# IDC_MCX_Adapter.net
KiCad netlist of a schematic drawn in Altium Designer
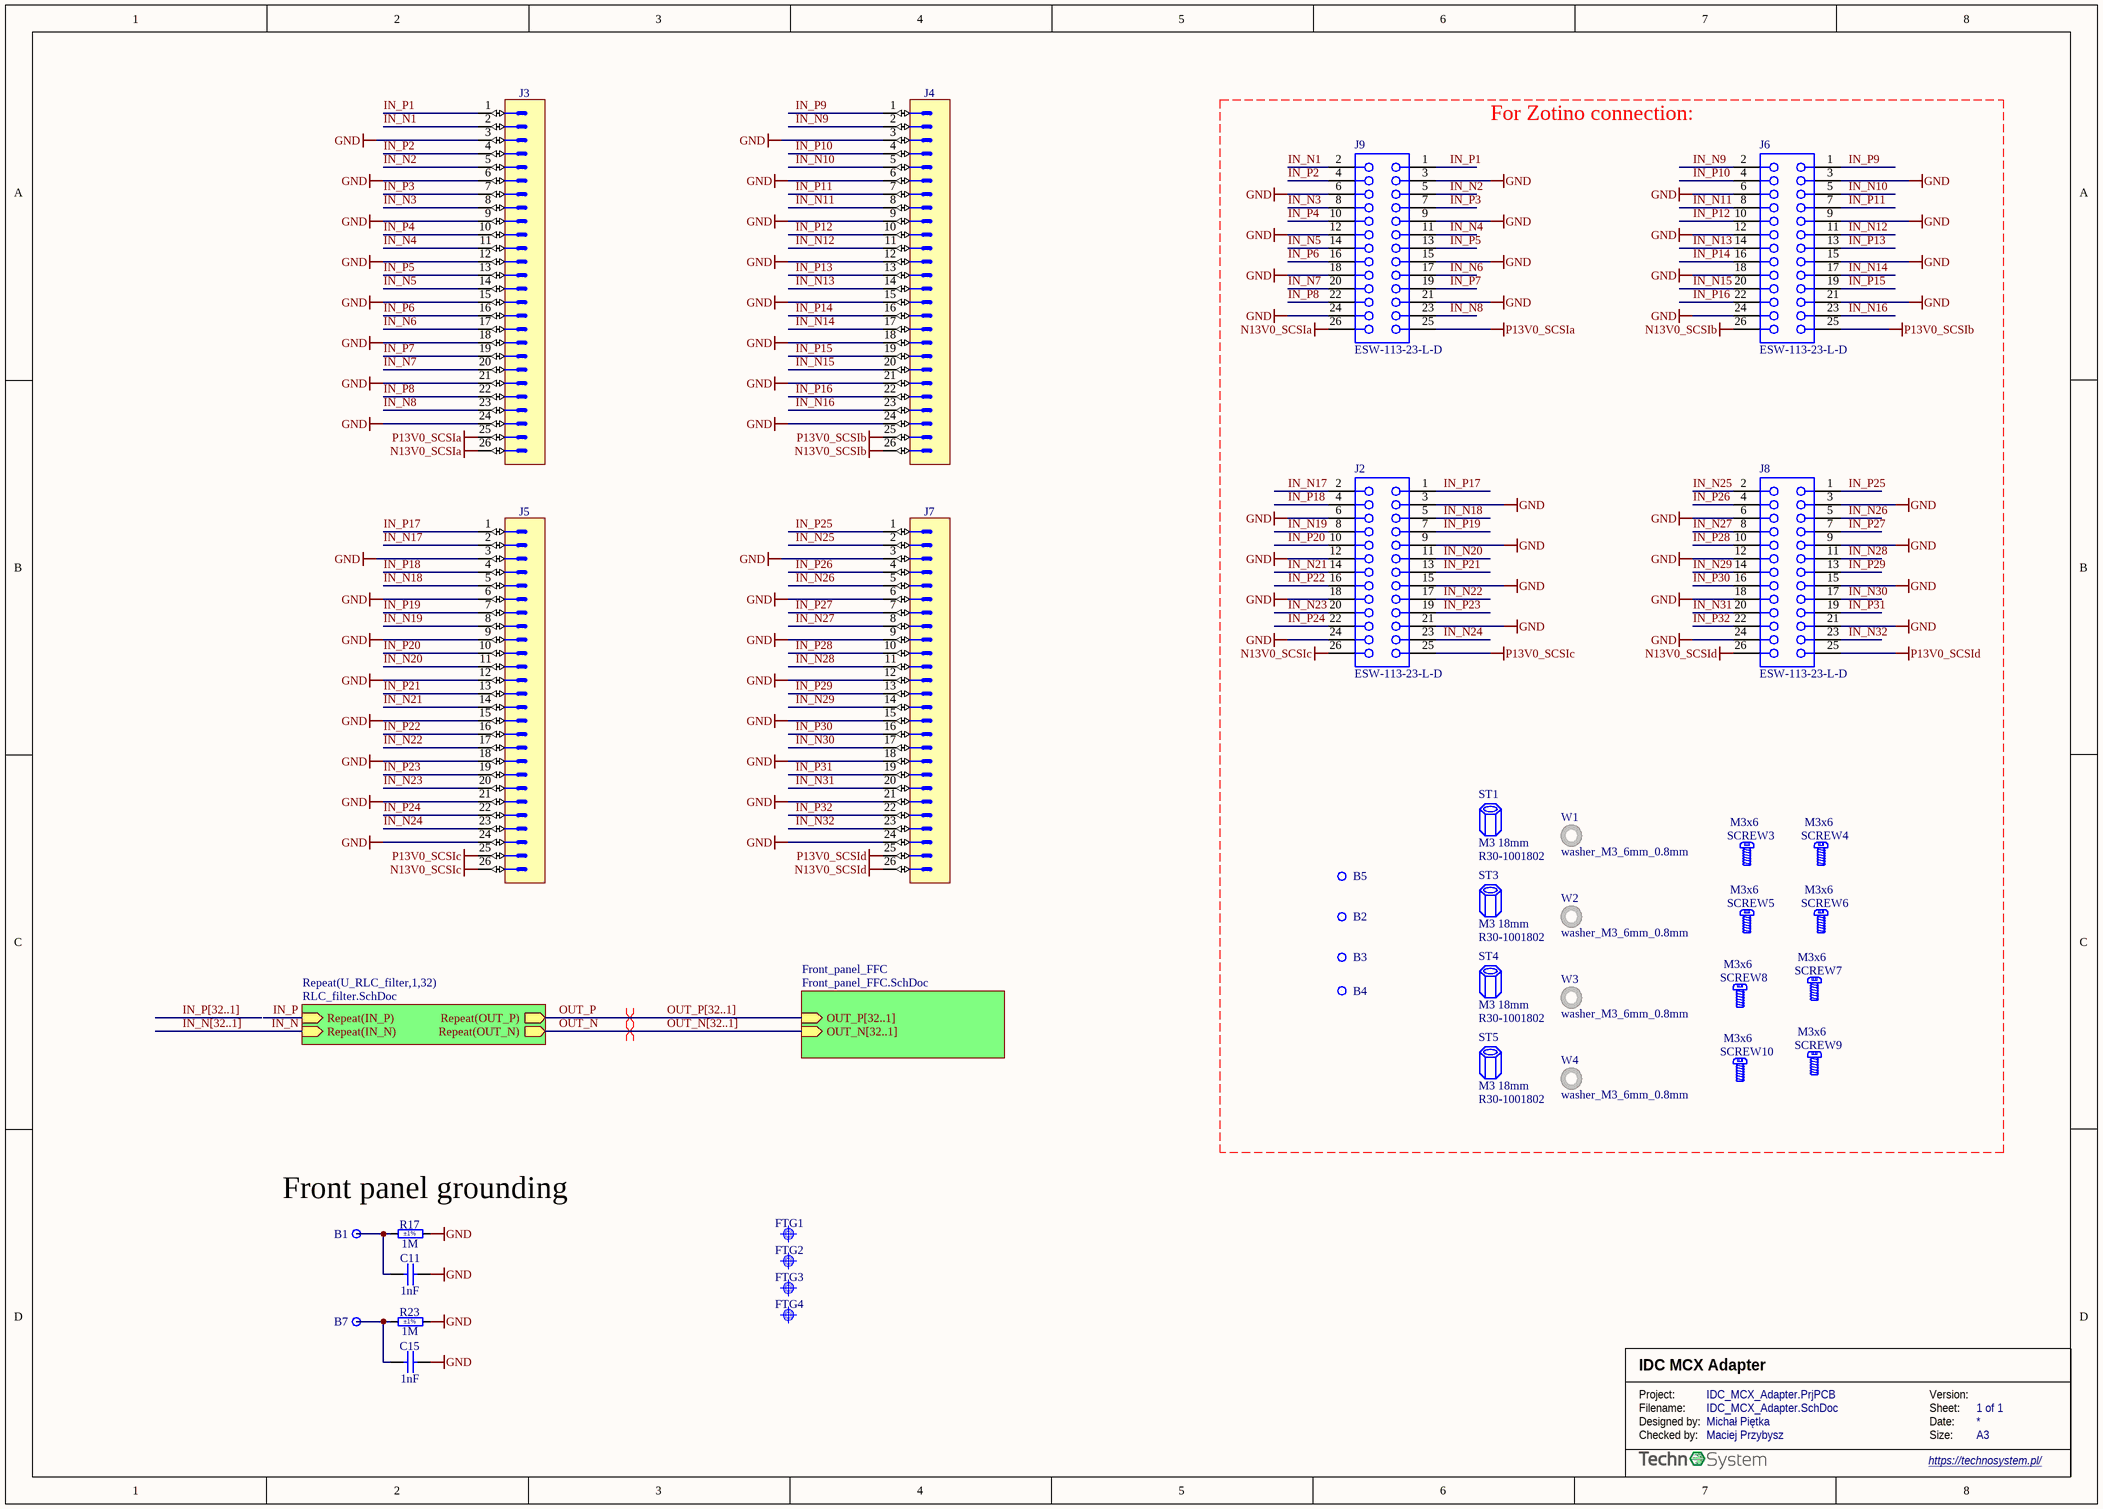
[diagram p0: IDC_MCX_Adapter.SchDoc]

(export (version "E")
  (design (tool "Eeschema 10.0.6"))
  (components
    (comp (ref "B1")
      (value "Plated Hole")
      (footprint "MTG270_500")
      (description "Single Terminal Socket")
      (fields (field (name "PART NUMBER") "PLATED_HOLE2.7_PAD5.0") (field (name "AUTHOR") "CERN DEM JMW"))
      (libsource (lib "Eletro-mechanical") (part "Single Terminal Socket"))
    )
    (comp (ref "B2")
      (value "Plated Hole")
      (footprint "MTG320_700")
      (description "Single Terminal Socket")
      (fields (field (name "PART NUMBER") "PLATED_HOLE3.2_PAD7.0") (field (name "AUTHOR") "CERN DEM JMW"))
      (libsource (lib "Eletro-mechanical") (part "Single Terminal Socket"))
    )
    (comp (ref "B3")
      (value "Plated Hole")
      (footprint "MTG320_700")
      (description "Single Terminal Socket")
      (fields (field (name "PART NUMBER") "PLATED_HOLE3.2_PAD7.0") (field (name "AUTHOR") "CERN DEM JMW"))
      (libsource (lib "Eletro-mechanical") (part "Single Terminal Socket"))
    )
    (comp (ref "B4")
      (value "Plated Hole")
      (footprint "MTG320_700")
      (description "Single Terminal Socket")
      (fields (field (name "PART NUMBER") "PLATED_HOLE3.2_PAD7.0") (field (name "AUTHOR") "CERN DEM JMW"))
      (libsource (lib "Eletro-mechanical") (part "Single Terminal Socket"))
    )
    (comp (ref "B5")
      (value "Plated Hole")
      (footprint "MTG320_700")
      (description "Single Terminal Socket")
      (fields (field (name "PART NUMBER") "PLATED_HOLE3.2_PAD7.0") (field (name "AUTHOR") "CERN DEM JMW"))
      (libsource (lib "Eletro-mechanical") (part "Single Terminal Socket"))
    )
    (comp (ref "B7")
      (value "Plated Hole")
      (footprint "MTG270_500")
      (description "Single Terminal Socket")
      (fields (field (name "PART NUMBER") "PLATED_HOLE2.7_PAD5.0") (field (name "AUTHOR") "CERN DEM JMW"))
      (libsource (lib "Eletro-mechanical") (part "Single Terminal Socket"))
    )
    (comp (ref "C11")
      (value "1nF")
      (footprint "CAPC1608X87N")
      (description "Non-polarised capacitor")
      (fields
        (field (name "PART NUMBER") "CC0603_1NF_50V_10%_X7R")
        (field (name "MANUFACTURER") "GENERIC")
        (field (name "AUTHOR") "CERN DEM JLC")
      )
      (libsource (lib "Capacitors") (part "Capacitor - non polarized"))
    )
    (comp (ref "C15")
      (value "1nF")
      (footprint "CAPC1608X87N")
      (description "Non-polarised capacitor")
      (fields
        (field (name "PART NUMBER") "CC0603_1NF_50V_10%_X7R")
        (field (name "MANUFACTURER") "GENERIC")
        (field (name "AUTHOR") "CERN DEM JLC")
      )
      (libsource (lib "Capacitors") (part "Capacitor - non polarized"))
    )
    (comp (ref "FTG1")
      (value "Use only in PCB")
      (footprint "FIDUCIAL_TOP_C100-200")
      (description "Fiducial Target")
      (fields (field (name "PART NUMBER") "FIDUCIAL_TARGET_C100-200") (field (name "AUTHOR") "CERN DEM JLC"))
      (libsource (lib "Eletro-mechanical") (part "Fiducial Target"))
    )
    (comp (ref "FTG2")
      (value "Use only in PCB")
      (footprint "FIDUCIAL_TOP_S100-200")
      (description "Fiducial Target")
      (fields (field (name "PART NUMBER") "FIDUCIAL_TARGET_S100-200") (field (name "AUTHOR") "CERN DEM JLC"))
      (libsource (lib "Eletro-mechanical") (part "Fiducial Target"))
    )
    (comp (ref "FTG3")
      (value "Use only in PCB")
      (footprint "FIDUCIAL_TOP_S100-200")
      (description "Fiducial Target")
      (fields (field (name "PART NUMBER") "FIDUCIAL_TARGET_S100-200") (field (name "AUTHOR") "CERN DEM JLC"))
      (libsource (lib "Eletro-mechanical") (part "Fiducial Target"))
    )
    (comp (ref "FTG4")
      (value "Use only in PCB")
      (footprint "FIDUCIAL_TOP_S100-200")
      (description "Fiducial Target")
      (fields (field (name "PART NUMBER") "FIDUCIAL_TARGET_S100-200") (field (name "AUTHOR") "CERN DEM JLC"))
      (libsource (lib "Eletro-mechanical") (part "Fiducial Target"))
    )
    (comp (ref "J2")
      (value "ESW-113-23-L-D")
      (footprint "SMTC-ESW-113-23-X-D")
      (description "Elevated Socket, Through-hole, Vertical, -55 to 125 degC, 2.54 mm Pitch, 26-Pin, Female, RoHS")
      (fields (field (name "MANUFACTURER") "Samtec"))
      (libsource (lib "Altium Content Vault") (part "SMTC-ESW-113-X-X-D"))
    )
    (comp (ref "J3")
      (value "Header 26")
      (footprint "3M_N2526-6002RB")
      (description "Connector 26 Male")
      (fields
        (field (name "PART NUMBER") "3M_N2526-6002RB")
        (field (name "MANUFACTURER") "3M")
        (field (name "AUTHOR") "CERN DEM JLC")
      )
      (libsource (lib "Connectors") (part "Connector 26 Male"))
    )
    (comp (ref "J4")
      (value "Header 26")
      (footprint "3M_N2526-6002RB")
      (description "Connector 26 Male")
      (fields
        (field (name "PART NUMBER") "3M_N2526-6002RB")
        (field (name "MANUFACTURER") "3M")
        (field (name "AUTHOR") "CERN DEM JLC")
      )
      (libsource (lib "Connectors") (part "Connector 26 Male"))
    )
    (comp (ref "J5")
      (value "Header 26")
      (footprint "3M_N2526-6002RB")
      (description "Connector 26 Male")
      (fields
        (field (name "PART NUMBER") "3M_N2526-6002RB")
        (field (name "MANUFACTURER") "3M")
        (field (name "AUTHOR") "CERN DEM JLC")
      )
      (libsource (lib "Connectors") (part "Connector 26 Male"))
    )
    (comp (ref "J6")
      (value "ESW-113-23-L-D")
      (footprint "SMTC-ESW-113-23-X-D")
      (description "Elevated Socket, Through-hole, Vertical, -55 to 125 degC, 2.54 mm Pitch, 26-Pin, Female, RoHS")
      (fields (field (name "MANUFACTURER") "Samtec"))
      (libsource (lib "Altium Content Vault") (part "SMTC-ESW-113-X-X-D"))
    )
    (comp (ref "J7")
      (value "Header 26")
      (footprint "3M_N2526-6002RB")
      (description "Connector 26 Male")
      (fields
        (field (name "PART NUMBER") "3M_N2526-6002RB")
        (field (name "MANUFACTURER") "3M")
        (field (name "AUTHOR") "CERN DEM JLC")
      )
      (libsource (lib "Connectors") (part "Connector 26 Male"))
    )
    (comp (ref "J8")
      (value "ESW-113-23-L-D")
      (footprint "SMTC-ESW-113-23-X-D")
      (description "Elevated Socket, Through-hole, Vertical, -55 to 125 degC, 2.54 mm Pitch, 26-Pin, Female, RoHS")
      (fields (field (name "MANUFACTURER") "Samtec"))
      (libsource (lib "Altium Content Vault") (part "SMTC-ESW-113-X-X-D"))
    )
    (comp (ref "J9")
      (value "ESW-113-23-L-D")
      (footprint "SMTC-ESW-113-23-X-D")
      (description "Elevated Socket, Through-hole, Vertical, -55 to 125 degC, 2.54 mm Pitch, 26-Pin, Female, RoHS")
      (fields (field (name "MANUFACTURER") "Samtec"))
      (libsource (lib "Altium Content Vault") (part "SMTC-ESW-113-X-X-D"))
    )
    (comp (ref "R17")
      (value "1M")
      (footprint "RESC1608X55N")
      (description "Resistor - 1%")
      (fields
        (field (name "PART NUMBER") "R0603_1M_1%_0.1W_100PPM")
        (field (name "MANUFACTURER") "GENERIC")
        (field (name "TOLERANCE") "±1%")
        (field (name "AUTHOR") "CERN DEM JLC")
      )
      (libsource (lib "Resistors") (part "Resistor - 1%"))
    )
    (comp (ref "R23")
      (value "1M")
      (footprint "RESC1608X55N")
      (description "Resistor - 1%")
      (fields
        (field (name "PART NUMBER") "R0603_1M_1%_0.1W_100PPM")
        (field (name "MANUFACTURER") "GENERIC")
        (field (name "TOLERANCE") "±1%")
        (field (name "AUTHOR") "CERN DEM JLC")
      )
      (libsource (lib "Resistors") (part "Resistor - 1%"))
    )
    (comp (ref "SCREW3")
      (value "M3x6")
      (footprint "BOSSARD_BN5687-3061605_v")
      (description "Screw")
      (fields
        (field (name "PART NUMBER") "BOSSARD_BN5687-3061605_v")
        (field (name "MANUFACTURER") "BOSSARD")
        (field (name "AUTHOR") "CERN DEM JLC")
      )
      (libsource (lib "Eletro-mechanical") (part "Screw"))
    )
    (comp (ref "SCREW4")
      (value "M3x6")
      (footprint "BOSSARD_BN5687-3061605_v")
      (description "Screw")
      (fields
        (field (name "PART NUMBER") "BOSSARD_BN5687-3061605_v")
        (field (name "MANUFACTURER") "BOSSARD")
        (field (name "AUTHOR") "CERN DEM JLC")
      )
      (libsource (lib "Eletro-mechanical") (part "Screw"))
    )
    (comp (ref "SCREW5")
      (value "M3x6")
      (footprint "BOSSARD_BN5687-3061605_v")
      (description "Screw")
      (fields
        (field (name "PART NUMBER") "BOSSARD_BN5687-3061605_v")
        (field (name "MANUFACTURER") "BOSSARD")
        (field (name "AUTHOR") "CERN DEM JLC")
      )
      (libsource (lib "Eletro-mechanical") (part "Screw"))
    )
    (comp (ref "SCREW6")
      (value "M3x6")
      (footprint "BOSSARD_BN5687-3061605_v")
      (description "Screw")
      (fields
        (field (name "PART NUMBER") "BOSSARD_BN5687-3061605_v")
        (field (name "MANUFACTURER") "BOSSARD")
        (field (name "AUTHOR") "CERN DEM JLC")
      )
      (libsource (lib "Eletro-mechanical") (part "Screw"))
    )
    (comp (ref "SCREW7")
      (value "M3x6")
      (footprint "BOSSARD_BN5687-3061605_v")
      (description "Screw")
      (fields
        (field (name "PART NUMBER") "BOSSARD_BN5687-3061605_v")
        (field (name "MANUFACTURER") "BOSSARD")
        (field (name "AUTHOR") "CERN DEM JLC")
      )
      (libsource (lib "Eletro-mechanical") (part "Screw"))
    )
    (comp (ref "SCREW8")
      (value "M3x6")
      (footprint "BOSSARD_BN5687-3061605_v")
      (description "Screw")
      (fields
        (field (name "PART NUMBER") "BOSSARD_BN5687-3061605_v")
        (field (name "MANUFACTURER") "BOSSARD")
        (field (name "AUTHOR") "CERN DEM JLC")
      )
      (libsource (lib "Eletro-mechanical") (part "Screw"))
    )
    (comp (ref "SCREW9")
      (value "M3x6")
      (footprint "BOSSARD_BN5687-3061605_v")
      (description "Screw")
      (fields
        (field (name "PART NUMBER") "BOSSARD_BN5687-3061605_v")
        (field (name "MANUFACTURER") "BOSSARD")
        (field (name "AUTHOR") "CERN DEM JLC")
      )
      (libsource (lib "Eletro-mechanical") (part "Screw"))
    )
    (comp (ref "SCREW10")
      (value "M3x6")
      (footprint "BOSSARD_BN5687-3061605_v")
      (description "Screw")
      (fields
        (field (name "PART NUMBER") "BOSSARD_BN5687-3061605_v")
        (field (name "MANUFACTURER") "BOSSARD")
        (field (name "AUTHOR") "CERN DEM JLC")
      )
      (libsource (lib "Eletro-mechanical") (part "Screw"))
    )
    (comp (ref "ST1")
      (value "M3 18mm")
      (footprint "R30-1001802")
      (description "M3.0x18 standoff")
      (fields (field (name "MANUFACTURER") "Harwin") (field (name "MANUFACTURER PART NUMBER") "R30-1001802"))
      (libsource (lib "mechanical") (part "STANDOFF_HARWIN_R30_1001802"))
    )
    (comp (ref "ST3")
      (value "M3 18mm")
      (footprint "R30-1001802")
      (description "M3.0x18 standoff")
      (fields (field (name "MANUFACTURER") "Harwin") (field (name "MANUFACTURER PART NUMBER") "R30-1001802"))
      (libsource (lib "mechanical") (part "STANDOFF_HARWIN_R30_1001802"))
    )
    (comp (ref "ST4")
      (value "M3 18mm")
      (footprint "R30-1001802")
      (description "M3.0x18 standoff")
      (fields (field (name "MANUFACTURER") "Harwin") (field (name "MANUFACTURER PART NUMBER") "R30-1001802"))
      (libsource (lib "mechanical") (part "STANDOFF_HARWIN_R30_1001802"))
    )
    (comp (ref "ST5")
      (value "M3 18mm")
      (footprint "R30-1001802")
      (description "M3.0x18 standoff")
      (fields (field (name "MANUFACTURER") "Harwin") (field (name "MANUFACTURER PART NUMBER") "R30-1001802"))
      (libsource (lib "mechanical") (part "STANDOFF_HARWIN_R30_1001802"))
    )
    (comp (ref "W1")
      (value "washer_M3_6mm_0.8mm")
      (footprint "washer_M3_6mm_0.8mm")
      (description "M3 Washer:\r\nID: 3.2mm\r\nOD: 6mm\r\nThickness 0.8mm")
      (fields
        (field (name "MANUFACTURER") "Accu Limited")
        (field (name "MANUFACTURER PART NUMBER") "HAFZ-M3-A4")
      )
      (libsource (lib "mechanical") (part "washer_M3_6mm_0.8mm"))
    )
    (comp (ref "W2")
      (value "washer_M3_6mm_0.8mm")
      (footprint "washer_M3_6mm_0.8mm")
      (description "M3 Washer:\r\nID: 3.2mm\r\nOD: 6mm\r\nThickness 0.8mm")
      (fields
        (field (name "MANUFACTURER") "Accu Limited")
        (field (name "MANUFACTURER PART NUMBER") "HAFZ-M3-A4")
      )
      (libsource (lib "mechanical") (part "washer_M3_6mm_0.8mm"))
    )
    (comp (ref "W3")
      (value "washer_M3_6mm_0.8mm")
      (footprint "washer_M3_6mm_0.8mm")
      (description "M3 Washer:\r\nID: 3.2mm\r\nOD: 6mm\r\nThickness 0.8mm")
      (fields
        (field (name "MANUFACTURER") "Accu Limited")
        (field (name "MANUFACTURER PART NUMBER") "HAFZ-M3-A4")
      )
      (libsource (lib "mechanical") (part "washer_M3_6mm_0.8mm"))
    )
    (comp (ref "W4")
      (value "washer_M3_6mm_0.8mm")
      (footprint "washer_M3_6mm_0.8mm")
      (description "M3 Washer:\r\nID: 3.2mm\r\nOD: 6mm\r\nThickness 0.8mm")
      (fields
        (field (name "MANUFACTURER") "Accu Limited")
        (field (name "MANUFACTURER PART NUMBER") "HAFZ-M3-A4")
      )
      (libsource (lib "mechanical") (part "washer_M3_6mm_0.8mm"))
    )
  )
  (nets
    (net (code "66") (name "/IN_N1") (class "Default")
      (node (ref "J3") (pin "2") (pinfunction "2_2") (pintype "bidirectional"))
      (node (ref "J9") (pin "2") (pinfunction "2_2") (pintype "passive"))
    )
    (net (code "67") (name "/IN_N2") (class "Default")
      (node (ref "J3") (pin "5") (pinfunction "5_5") (pintype "bidirectional"))
      (node (ref "J9") (pin "5") (pinfunction "5_5") (pintype "passive"))
    )
    (net (code "68") (name "/IN_N3") (class "Default")
      (node (ref "J3") (pin "8") (pinfunction "8_8") (pintype "bidirectional"))
      (node (ref "J9") (pin "8") (pinfunction "8_8") (pintype "passive"))
    )
    (net (code "69") (name "/IN_N4") (class "Default")
      (node (ref "J3") (pin "11") (pinfunction "11_11") (pintype "bidirectional"))
      (node (ref "J9") (pin "11") (pinfunction "11_11") (pintype "passive"))
    )
    (net (code "70") (name "/IN_N5") (class "Default")
      (node (ref "J3") (pin "14") (pinfunction "14_14") (pintype "bidirectional"))
      (node (ref "J9") (pin "14") (pinfunction "14_14") (pintype "passive"))
    )
    (net (code "71") (name "/IN_N6") (class "Default")
      (node (ref "J3") (pin "17") (pinfunction "17_17") (pintype "bidirectional"))
      (node (ref "J9") (pin "17") (pinfunction "17_17") (pintype "passive"))
    )
    (net (code "72") (name "/IN_N7") (class "Default")
      (node (ref "J3") (pin "20") (pinfunction "20_20") (pintype "bidirectional"))
      (node (ref "J9") (pin "20") (pinfunction "20_20") (pintype "passive"))
    )
    (net (code "73") (name "/IN_N8") (class "Default")
      (node (ref "J3") (pin "23") (pinfunction "23_23") (pintype "bidirectional"))
      (node (ref "J9") (pin "23") (pinfunction "23_23") (pintype "passive"))
    )
    (net (code "74") (name "/IN_N9") (class "Default")
      (node (ref "J4") (pin "2") (pinfunction "2_2") (pintype "bidirectional"))
      (node (ref "J6") (pin "2") (pinfunction "2_2") (pintype "passive"))
    )
    (net (code "75") (name "/IN_N10") (class "Default")
      (node (ref "J4") (pin "5") (pinfunction "5_5") (pintype "bidirectional"))
      (node (ref "J6") (pin "5") (pinfunction "5_5") (pintype "passive"))
    )
    (net (code "76") (name "/IN_N11") (class "Default")
      (node (ref "J4") (pin "8") (pinfunction "8_8") (pintype "bidirectional"))
      (node (ref "J6") (pin "8") (pinfunction "8_8") (pintype "passive"))
    )
    (net (code "77") (name "/IN_N12") (class "Default")
      (node (ref "J4") (pin "11") (pinfunction "11_11") (pintype "bidirectional"))
      (node (ref "J6") (pin "11") (pinfunction "11_11") (pintype "passive"))
    )
    (net (code "78") (name "/IN_N13") (class "Default")
      (node (ref "J4") (pin "14") (pinfunction "14_14") (pintype "bidirectional"))
      (node (ref "J6") (pin "14") (pinfunction "14_14") (pintype "passive"))
    )
    (net (code "79") (name "/IN_N14") (class "Default")
      (node (ref "J4") (pin "17") (pinfunction "17_17") (pintype "bidirectional"))
      (node (ref "J6") (pin "17") (pinfunction "17_17") (pintype "passive"))
    )
    (net (code "80") (name "/IN_N15") (class "Default")
      (node (ref "J4") (pin "20") (pinfunction "20_20") (pintype "bidirectional"))
      (node (ref "J6") (pin "20") (pinfunction "20_20") (pintype "passive"))
    )
    (net (code "81") (name "/IN_N16") (class "Default")
      (node (ref "J4") (pin "23") (pinfunction "23_23") (pintype "bidirectional"))
      (node (ref "J6") (pin "23") (pinfunction "23_23") (pintype "passive"))
    )
    (net (code "82") (name "/IN_N17") (class "Default")
      (node (ref "J2") (pin "2") (pinfunction "2_2") (pintype "passive"))
      (node (ref "J5") (pin "2") (pinfunction "2_2") (pintype "bidirectional"))
    )
    (net (code "83") (name "/IN_N18") (class "Default")
      (node (ref "J2") (pin "5") (pinfunction "5_5") (pintype "passive"))
      (node (ref "J5") (pin "5") (pinfunction "5_5") (pintype "bidirectional"))
    )
    (net (code "84") (name "/IN_N19") (class "Default")
      (node (ref "J2") (pin "8") (pinfunction "8_8") (pintype "passive"))
      (node (ref "J5") (pin "8") (pinfunction "8_8") (pintype "bidirectional"))
    )
    (net (code "85") (name "/IN_N20") (class "Default")
      (node (ref "J2") (pin "11") (pinfunction "11_11") (pintype "passive"))
      (node (ref "J5") (pin "11") (pinfunction "11_11") (pintype "bidirectional"))
    )
    (net (code "86") (name "/IN_N21") (class "Default")
      (node (ref "J2") (pin "14") (pinfunction "14_14") (pintype "passive"))
      (node (ref "J5") (pin "14") (pinfunction "14_14") (pintype "bidirectional"))
    )
    (net (code "87") (name "/IN_N22") (class "Default")
      (node (ref "J2") (pin "17") (pinfunction "17_17") (pintype "passive"))
      (node (ref "J5") (pin "17") (pinfunction "17_17") (pintype "bidirectional"))
    )
    (net (code "88") (name "/IN_N23") (class "Default")
      (node (ref "J2") (pin "20") (pinfunction "20_20") (pintype "passive"))
      (node (ref "J5") (pin "20") (pinfunction "20_20") (pintype "bidirectional"))
    )
    (net (code "89") (name "/IN_N24") (class "Default")
      (node (ref "J2") (pin "23") (pinfunction "23_23") (pintype "passive"))
      (node (ref "J5") (pin "23") (pinfunction "23_23") (pintype "bidirectional"))
    )
    (net (code "90") (name "/IN_N25") (class "Default")
      (node (ref "J7") (pin "2") (pinfunction "2_2") (pintype "bidirectional"))
      (node (ref "J8") (pin "2") (pinfunction "2_2") (pintype "passive"))
    )
    (net (code "91") (name "/IN_N26") (class "Default")
      (node (ref "J7") (pin "5") (pinfunction "5_5") (pintype "bidirectional"))
      (node (ref "J8") (pin "5") (pinfunction "5_5") (pintype "passive"))
    )
    (net (code "92") (name "/IN_N27") (class "Default")
      (node (ref "J7") (pin "8") (pinfunction "8_8") (pintype "bidirectional"))
      (node (ref "J8") (pin "8") (pinfunction "8_8") (pintype "passive"))
    )
    (net (code "93") (name "/IN_N28") (class "Default")
      (node (ref "J7") (pin "11") (pinfunction "11_11") (pintype "bidirectional"))
      (node (ref "J8") (pin "11") (pinfunction "11_11") (pintype "passive"))
    )
    (net (code "94") (name "/IN_N29") (class "Default")
      (node (ref "J7") (pin "14") (pinfunction "14_14") (pintype "bidirectional"))
      (node (ref "J8") (pin "14") (pinfunction "14_14") (pintype "passive"))
    )
    (net (code "95") (name "/IN_N30") (class "Default")
      (node (ref "J7") (pin "17") (pinfunction "17_17") (pintype "bidirectional"))
      (node (ref "J8") (pin "17") (pinfunction "17_17") (pintype "passive"))
    )
    (net (code "96") (name "/IN_N31") (class "Default")
      (node (ref "J7") (pin "20") (pinfunction "20_20") (pintype "bidirectional"))
      (node (ref "J8") (pin "20") (pinfunction "20_20") (pintype "passive"))
    )
    (net (code "97") (name "/IN_N32") (class "Default")
      (node (ref "J7") (pin "23") (pinfunction "23_23") (pintype "bidirectional"))
      (node (ref "J8") (pin "23") (pinfunction "23_23") (pintype "passive"))
    )
    (net (code "100") (name "/IN_P1") (class "Default")
      (node (ref "J3") (pin "1") (pinfunction "1_1") (pintype "bidirectional"))
      (node (ref "J9") (pin "1") (pinfunction "1_1") (pintype "passive"))
    )
    (net (code "101") (name "/IN_P2") (class "Default")
      (node (ref "J3") (pin "4") (pinfunction "4_4") (pintype "bidirectional"))
      (node (ref "J9") (pin "4") (pinfunction "4_4") (pintype "passive"))
    )
    (net (code "102") (name "/IN_P3") (class "Default")
      (node (ref "J3") (pin "7") (pinfunction "7_7") (pintype "bidirectional"))
      (node (ref "J9") (pin "7") (pinfunction "7_7") (pintype "passive"))
    )
    (net (code "103") (name "/IN_P4") (class "Default")
      (node (ref "J3") (pin "10") (pinfunction "10_10") (pintype "bidirectional"))
      (node (ref "J9") (pin "10") (pinfunction "10_10") (pintype "passive"))
    )
    (net (code "104") (name "/IN_P5") (class "Default")
      (node (ref "J3") (pin "13") (pinfunction "13_13") (pintype "bidirectional"))
      (node (ref "J9") (pin "13") (pinfunction "13_13") (pintype "passive"))
    )
    (net (code "105") (name "/IN_P6") (class "Default")
      (node (ref "J3") (pin "16") (pinfunction "16_16") (pintype "bidirectional"))
      (node (ref "J9") (pin "16") (pinfunction "16_16") (pintype "passive"))
    )
    (net (code "106") (name "/IN_P7") (class "Default")
      (node (ref "J3") (pin "19") (pinfunction "19_19") (pintype "bidirectional"))
      (node (ref "J9") (pin "19") (pinfunction "19_19") (pintype "passive"))
    )
    (net (code "107") (name "/IN_P8") (class "Default")
      (node (ref "J3") (pin "22") (pinfunction "22_22") (pintype "bidirectional"))
      (node (ref "J9") (pin "22") (pinfunction "22_22") (pintype "passive"))
    )
    (net (code "108") (name "/IN_P9") (class "Default")
      (node (ref "J4") (pin "1") (pinfunction "1_1") (pintype "bidirectional"))
      (node (ref "J6") (pin "1") (pinfunction "1_1") (pintype "passive"))
    )
    (net (code "109") (name "/IN_P10") (class "Default")
      (node (ref "J4") (pin "4") (pinfunction "4_4") (pintype "bidirectional"))
      (node (ref "J6") (pin "4") (pinfunction "4_4") (pintype "passive"))
    )
    (net (code "110") (name "/IN_P11") (class "Default")
      (node (ref "J4") (pin "7") (pinfunction "7_7") (pintype "bidirectional"))
      (node (ref "J6") (pin "7") (pinfunction "7_7") (pintype "passive"))
    )
    (net (code "111") (name "/IN_P12") (class "Default")
      (node (ref "J4") (pin "10") (pinfunction "10_10") (pintype "bidirectional"))
      (node (ref "J6") (pin "10") (pinfunction "10_10") (pintype "passive"))
    )
    (net (code "112") (name "/IN_P13") (class "Default")
      (node (ref "J4") (pin "13") (pinfunction "13_13") (pintype "bidirectional"))
      (node (ref "J6") (pin "13") (pinfunction "13_13") (pintype "passive"))
    )
    (net (code "113") (name "/IN_P14") (class "Default")
      (node (ref "J4") (pin "16") (pinfunction "16_16") (pintype "bidirectional"))
      (node (ref "J6") (pin "16") (pinfunction "16_16") (pintype "passive"))
    )
    (net (code "114") (name "/IN_P15") (class "Default")
      (node (ref "J4") (pin "19") (pinfunction "19_19") (pintype "bidirectional"))
      (node (ref "J6") (pin "19") (pinfunction "19_19") (pintype "passive"))
    )
    (net (code "115") (name "/IN_P16") (class "Default")
      (node (ref "J4") (pin "22") (pinfunction "22_22") (pintype "bidirectional"))
      (node (ref "J6") (pin "22") (pinfunction "22_22") (pintype "passive"))
    )
    (net (code "116") (name "/IN_P17") (class "Default")
      (node (ref "J2") (pin "1") (pinfunction "1_1") (pintype "passive"))
      (node (ref "J5") (pin "1") (pinfunction "1_1") (pintype "bidirectional"))
    )
    (net (code "117") (name "/IN_P18") (class "Default")
      (node (ref "J2") (pin "4") (pinfunction "4_4") (pintype "passive"))
      (node (ref "J5") (pin "4") (pinfunction "4_4") (pintype "bidirectional"))
    )
    (net (code "118") (name "/IN_P19") (class "Default")
      (node (ref "J2") (pin "7") (pinfunction "7_7") (pintype "passive"))
      (node (ref "J5") (pin "7") (pinfunction "7_7") (pintype "bidirectional"))
    )
    (net (code "119") (name "/IN_P20") (class "Default")
      (node (ref "J2") (pin "10") (pinfunction "10_10") (pintype "passive"))
      (node (ref "J5") (pin "10") (pinfunction "10_10") (pintype "bidirectional"))
    )
    (net (code "120") (name "/IN_P21") (class "Default")
      (node (ref "J2") (pin "13") (pinfunction "13_13") (pintype "passive"))
      (node (ref "J5") (pin "13") (pinfunction "13_13") (pintype "bidirectional"))
    )
    (net (code "121") (name "/IN_P22") (class "Default")
      (node (ref "J2") (pin "16") (pinfunction "16_16") (pintype "passive"))
      (node (ref "J5") (pin "16") (pinfunction "16_16") (pintype "bidirectional"))
    )
    (net (code "122") (name "/IN_P23") (class "Default")
      (node (ref "J2") (pin "19") (pinfunction "19_19") (pintype "passive"))
      (node (ref "J5") (pin "19") (pinfunction "19_19") (pintype "bidirectional"))
    )
    (net (code "123") (name "/IN_P24") (class "Default")
      (node (ref "J2") (pin "22") (pinfunction "22_22") (pintype "passive"))
      (node (ref "J5") (pin "22") (pinfunction "22_22") (pintype "bidirectional"))
    )
    (net (code "124") (name "/IN_P25") (class "Default")
      (node (ref "J7") (pin "1") (pinfunction "1_1") (pintype "bidirectional"))
      (node (ref "J8") (pin "1") (pinfunction "1_1") (pintype "passive"))
    )
    (net (code "125") (name "/IN_P26") (class "Default")
      (node (ref "J7") (pin "4") (pinfunction "4_4") (pintype "bidirectional"))
      (node (ref "J8") (pin "4") (pinfunction "4_4") (pintype "passive"))
    )
    (net (code "126") (name "/IN_P27") (class "Default")
      (node (ref "J7") (pin "7") (pinfunction "7_7") (pintype "bidirectional"))
      (node (ref "J8") (pin "7") (pinfunction "7_7") (pintype "passive"))
    )
    (net (code "127") (name "/IN_P28") (class "Default")
      (node (ref "J7") (pin "10") (pinfunction "10_10") (pintype "bidirectional"))
      (node (ref "J8") (pin "10") (pinfunction "10_10") (pintype "passive"))
    )
    (net (code "128") (name "/IN_P29") (class "Default")
      (node (ref "J7") (pin "13") (pinfunction "13_13") (pintype "bidirectional"))
      (node (ref "J8") (pin "13") (pinfunction "13_13") (pintype "passive"))
    )
    (net (code "129") (name "/IN_P30") (class "Default")
      (node (ref "J7") (pin "16") (pinfunction "16_16") (pintype "bidirectional"))
      (node (ref "J8") (pin "16") (pinfunction "16_16") (pintype "passive"))
    )
    (net (code "130") (name "/IN_P31") (class "Default")
      (node (ref "J7") (pin "19") (pinfunction "19_19") (pintype "bidirectional"))
      (node (ref "J8") (pin "19") (pinfunction "19_19") (pintype "passive"))
    )
    (net (code "131") (name "/IN_P32") (class "Default")
      (node (ref "J7") (pin "22") (pinfunction "22_22") (pintype "bidirectional"))
      (node (ref "J8") (pin "22") (pinfunction "22_22") (pintype "passive"))
    )
    (net (code "137") (name "GND") (class "Default")
      (node (ref "C11") (pin "2") (pinfunction "2_2") (pintype "passive"))
      (node (ref "C15") (pin "2") (pinfunction "2_2") (pintype "passive"))
      (node (ref "J2") (pin "12") (pinfunction "12_12") (pintype "passive"))
      (node (ref "J2") (pin "15") (pinfunction "15_15") (pintype "passive"))
      (node (ref "J2") (pin "18") (pinfunction "18_18") (pintype "passive"))
      (node (ref "J2") (pin "21") (pinfunction "21_21") (pintype "passive"))
      (node (ref "J2") (pin "24") (pinfunction "24_24") (pintype "passive"))
      (node (ref "J2") (pin "3") (pinfunction "3_3") (pintype "passive"))
      (node (ref "J2") (pin "6") (pinfunction "6_6") (pintype "passive"))
      (node (ref "J2") (pin "9") (pinfunction "9_9") (pintype "passive"))
      (node (ref "J3") (pin "12") (pinfunction "12_12") (pintype "bidirectional"))
      (node (ref "J3") (pin "15") (pinfunction "15_15") (pintype "bidirectional"))
      (node (ref "J3") (pin "18") (pinfunction "18_18") (pintype "bidirectional"))
      (node (ref "J3") (pin "21") (pinfunction "21_21") (pintype "bidirectional"))
      (node (ref "J3") (pin "24") (pinfunction "24_24") (pintype "bidirectional"))
      (node (ref "J3") (pin "3") (pinfunction "3_3") (pintype "bidirectional"))
      (node (ref "J3") (pin "6") (pinfunction "6_6") (pintype "bidirectional"))
      (node (ref "J3") (pin "9") (pinfunction "9_9") (pintype "bidirectional"))
      (node (ref "J4") (pin "12") (pinfunction "12_12") (pintype "bidirectional"))
      (node (ref "J4") (pin "15") (pinfunction "15_15") (pintype "bidirectional"))
      (node (ref "J4") (pin "18") (pinfunction "18_18") (pintype "bidirectional"))
      (node (ref "J4") (pin "21") (pinfunction "21_21") (pintype "bidirectional"))
      (node (ref "J4") (pin "24") (pinfunction "24_24") (pintype "bidirectional"))
      (node (ref "J4") (pin "3") (pinfunction "3_3") (pintype "bidirectional"))
      (node (ref "J4") (pin "6") (pinfunction "6_6") (pintype "bidirectional"))
      (node (ref "J4") (pin "9") (pinfunction "9_9") (pintype "bidirectional"))
      (node (ref "J5") (pin "12") (pinfunction "12_12") (pintype "bidirectional"))
      (node (ref "J5") (pin "15") (pinfunction "15_15") (pintype "bidirectional"))
      (node (ref "J5") (pin "18") (pinfunction "18_18") (pintype "bidirectional"))
      (node (ref "J5") (pin "21") (pinfunction "21_21") (pintype "bidirectional"))
      (node (ref "J5") (pin "24") (pinfunction "24_24") (pintype "bidirectional"))
      (node (ref "J5") (pin "3") (pinfunction "3_3") (pintype "bidirectional"))
      (node (ref "J5") (pin "6") (pinfunction "6_6") (pintype "bidirectional"))
      (node (ref "J5") (pin "9") (pinfunction "9_9") (pintype "bidirectional"))
      (node (ref "J6") (pin "12") (pinfunction "12_12") (pintype "passive"))
      (node (ref "J6") (pin "15") (pinfunction "15_15") (pintype "passive"))
      (node (ref "J6") (pin "18") (pinfunction "18_18") (pintype "passive"))
      (node (ref "J6") (pin "21") (pinfunction "21_21") (pintype "passive"))
      (node (ref "J6") (pin "24") (pinfunction "24_24") (pintype "passive"))
      (node (ref "J6") (pin "3") (pinfunction "3_3") (pintype "passive"))
      (node (ref "J6") (pin "6") (pinfunction "6_6") (pintype "passive"))
      (node (ref "J6") (pin "9") (pinfunction "9_9") (pintype "passive"))
      (node (ref "J7") (pin "12") (pinfunction "12_12") (pintype "bidirectional"))
      (node (ref "J7") (pin "15") (pinfunction "15_15") (pintype "bidirectional"))
      (node (ref "J7") (pin "18") (pinfunction "18_18") (pintype "bidirectional"))
      (node (ref "J7") (pin "21") (pinfunction "21_21") (pintype "bidirectional"))
      (node (ref "J7") (pin "24") (pinfunction "24_24") (pintype "bidirectional"))
      (node (ref "J7") (pin "3") (pinfunction "3_3") (pintype "bidirectional"))
      (node (ref "J7") (pin "6") (pinfunction "6_6") (pintype "bidirectional"))
      (node (ref "J7") (pin "9") (pinfunction "9_9") (pintype "bidirectional"))
      (node (ref "J8") (pin "12") (pinfunction "12_12") (pintype "passive"))
      (node (ref "J8") (pin "15") (pinfunction "15_15") (pintype "passive"))
      (node (ref "J8") (pin "18") (pinfunction "18_18") (pintype "passive"))
      (node (ref "J8") (pin "21") (pinfunction "21_21") (pintype "passive"))
      (node (ref "J8") (pin "24") (pinfunction "24_24") (pintype "passive"))
      (node (ref "J8") (pin "3") (pinfunction "3_3") (pintype "passive"))
      (node (ref "J8") (pin "6") (pinfunction "6_6") (pintype "passive"))
      (node (ref "J8") (pin "9") (pinfunction "9_9") (pintype "passive"))
      (node (ref "J9") (pin "12") (pinfunction "12_12") (pintype "passive"))
      (node (ref "J9") (pin "15") (pinfunction "15_15") (pintype "passive"))
      (node (ref "J9") (pin "18") (pinfunction "18_18") (pintype "passive"))
      (node (ref "J9") (pin "21") (pinfunction "21_21") (pintype "passive"))
      (node (ref "J9") (pin "24") (pinfunction "24_24") (pintype "passive"))
      (node (ref "J9") (pin "3") (pinfunction "3_3") (pintype "passive"))
      (node (ref "J9") (pin "6") (pinfunction "6_6") (pintype "passive"))
      (node (ref "J9") (pin "9") (pinfunction "9_9") (pintype "passive"))
      (node (ref "R17") (pin "2") (pinfunction "2_2") (pintype "passive"))
      (node (ref "R23") (pin "2") (pinfunction "2_2") (pintype "passive"))
    )
    (net (code "138") (name "N13V0_SCSIa") (class "Default")
      (node (ref "J3") (pin "26") (pinfunction "26_26") (pintype "bidirectional"))
      (node (ref "J9") (pin "26") (pinfunction "26_26") (pintype "passive"))
    )
    (net (code "139") (name "N13V0_SCSIb") (class "Default")
      (node (ref "J4") (pin "26") (pinfunction "26_26") (pintype "bidirectional"))
      (node (ref "J6") (pin "26") (pinfunction "26_26") (pintype "passive"))
    )
    (net (code "140") (name "N13V0_SCSIc") (class "Default")
      (node (ref "J2") (pin "26") (pinfunction "26_26") (pintype "passive"))
      (node (ref "J5") (pin "26") (pinfunction "26_26") (pintype "bidirectional"))
    )
    (net (code "141") (name "N13V0_SCSId") (class "Default")
      (node (ref "J7") (pin "26") (pinfunction "26_26") (pintype "bidirectional"))
      (node (ref "J8") (pin "26") (pinfunction "26_26") (pintype "passive"))
    )
    (net (code "142") (name "Net-(B1-Pad1)") (class "Default")
      (node (ref "B1") (pin "1") (pinfunction "1_1") (pintype "bidirectional"))
      (node (ref "C11") (pin "1") (pinfunction "1_1") (pintype "passive"))
      (node (ref "R17") (pin "1") (pinfunction "1_1") (pintype "passive"))
    )
    (net (code "143") (name "Net-(B7-Pad1)") (class "Default")
      (node (ref "B7") (pin "1") (pinfunction "1_1") (pintype "bidirectional"))
      (node (ref "C15") (pin "1") (pinfunction "1_1") (pintype "passive"))
      (node (ref "R23") (pin "1") (pinfunction "1_1") (pintype "passive"))
    )
    (net (code "144") (name "P13V0_SCSIa") (class "Default")
      (node (ref "J3") (pin "25") (pinfunction "25_25") (pintype "bidirectional"))
      (node (ref "J9") (pin "25") (pinfunction "25_25") (pintype "passive"))
    )
    (net (code "145") (name "P13V0_SCSIb") (class "Default")
      (node (ref "J4") (pin "25") (pinfunction "25_25") (pintype "bidirectional"))
      (node (ref "J6") (pin "25") (pinfunction "25_25") (pintype "passive"))
    )
    (net (code "146") (name "P13V0_SCSIc") (class "Default")
      (node (ref "J2") (pin "25") (pinfunction "25_25") (pintype "passive"))
      (node (ref "J5") (pin "25") (pinfunction "25_25") (pintype "bidirectional"))
    )
    (net (code "147") (name "P13V0_SCSId") (class "Default")
      (node (ref "J7") (pin "25") (pinfunction "25_25") (pintype "bidirectional"))
      (node (ref "J8") (pin "25") (pinfunction "25_25") (pintype "passive"))
    )
    (net (code "148") (name "unconnected-(B2-Pad1)") (class "Default")
      (node (ref "B2") (pin "1") (pinfunction "1_1") (pintype "bidirectional"))
    )
    (net (code "149") (name "unconnected-(B3-Pad1)") (class "Default")
      (node (ref "B3") (pin "1") (pinfunction "1_1") (pintype "bidirectional"))
    )
    (net (code "150") (name "unconnected-(B4-Pad1)") (class "Default")
      (node (ref "B4") (pin "1") (pinfunction "1_1") (pintype "bidirectional"))
    )
    (net (code "151") (name "unconnected-(B5-Pad1)") (class "Default")
      (node (ref "B5") (pin "1") (pinfunction "1_1") (pintype "bidirectional"))
    )
  )
)
